# Teensy.net
KiCad netlist of a schematic drawn in Altium Designer
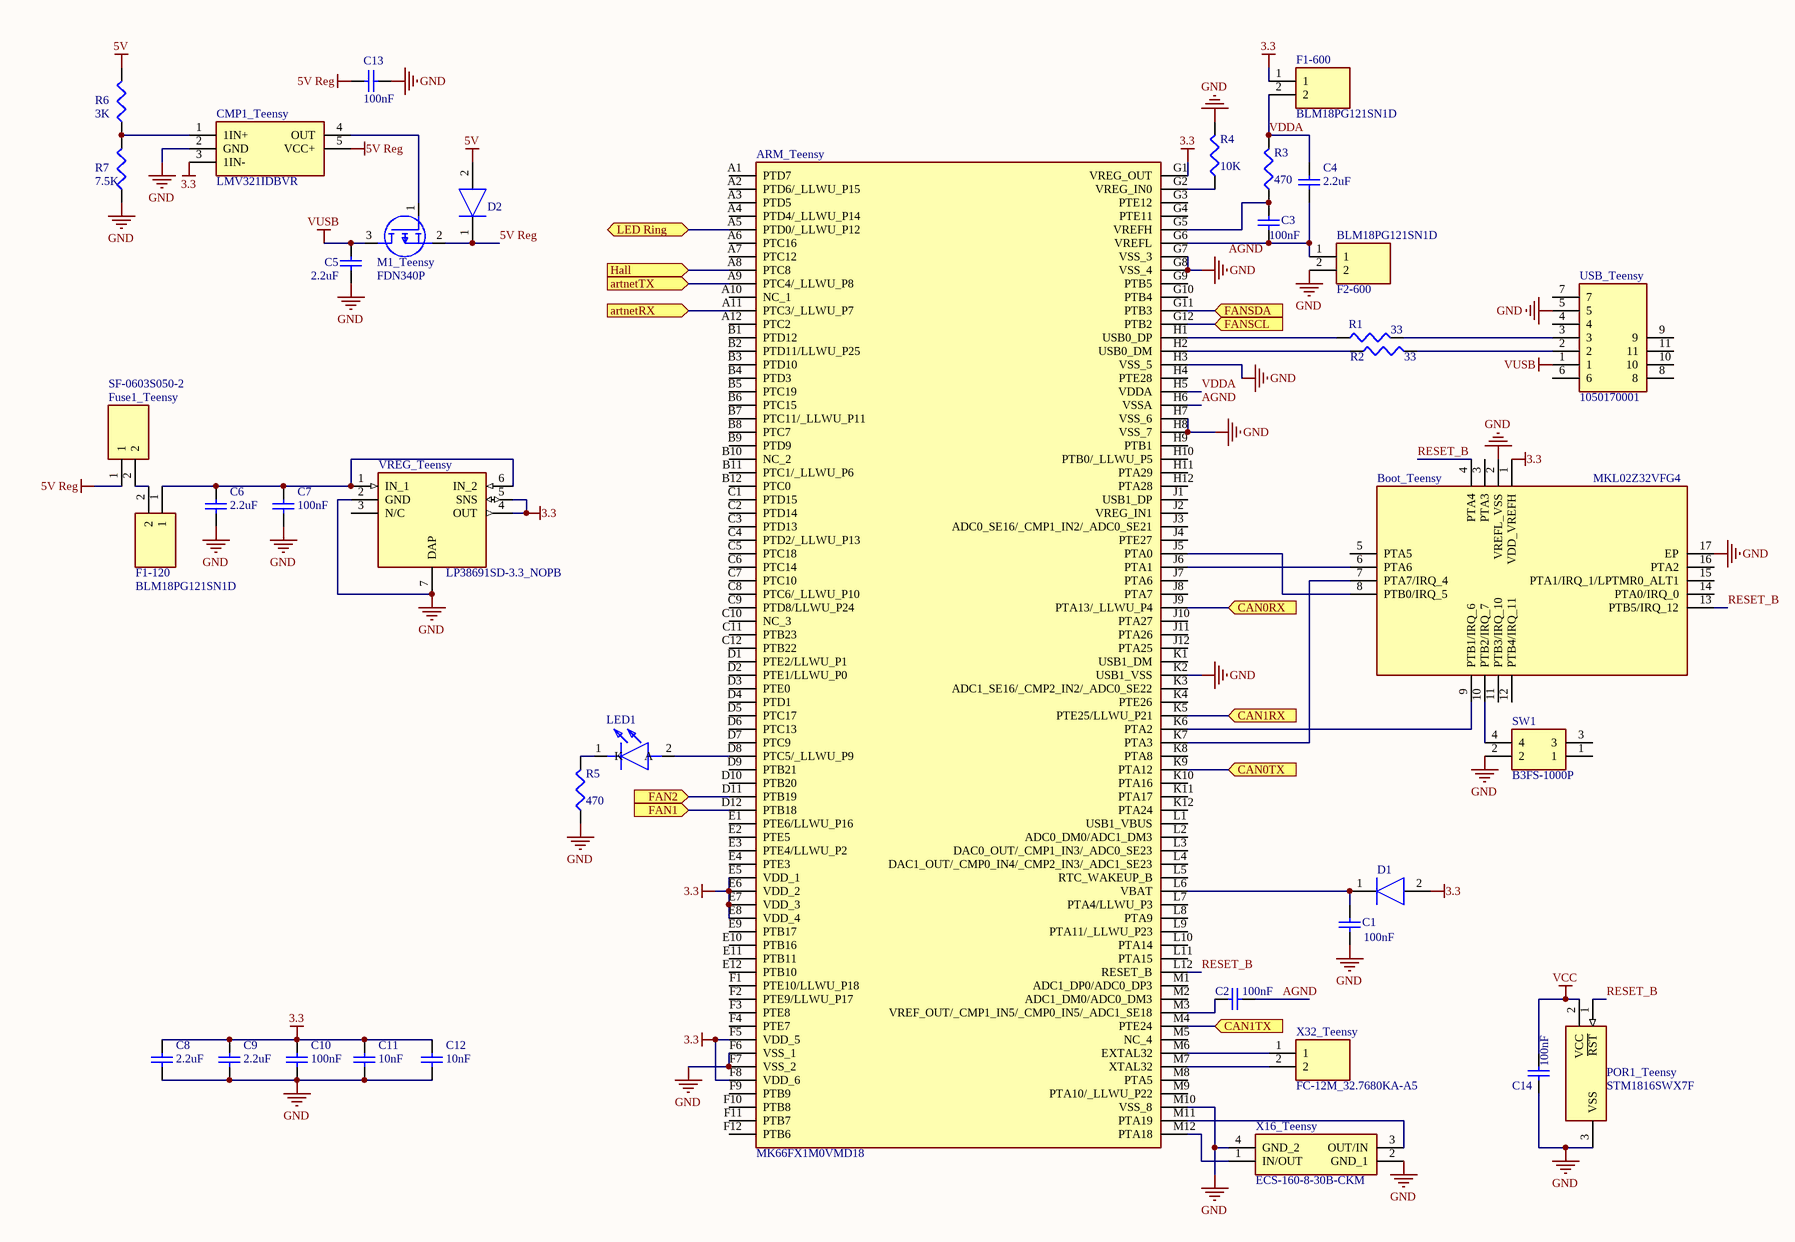
[diagram p0: Teensy.SchDoc]

(export (version "E")
  (design (tool "Eeschema 10.0.6"))
  (components
    (comp (ref "ARM_Teensy")
      (value "MK66FX1M0VMD18")
      (footprint "LX1-Teensy:BGA144C100P12X12_1300X1300X170")
      (description "Integrated Circuit")
      (fields (field (name "MOUSER PART NUMBER") "841-MK66FX1M0VMD18"))
      (libsource (lib "LX1-Teensy") (part "MK66FX1M0VMD18"))
    )
    (comp (ref "Boot_Teensy")
      (value "MKL02Z32VFG4")
      (footprint "LX1-Teensy:QFN50P300X300X65-17N-D")
      (description "Integrated Circuit")
      (fields
        (field (name "MOUSER PART NUMBER") "841-MKL02Z32VFG4")
        (field (name "RS PART NUMBER") "7884723P")
      )
      (libsource (lib "LX1-Teensy") (part "MKL02Z32VFG4"))
    )
    (comp (ref "C1")
      (value "100nF")
      (footprint "1608[0603]")
      (description "Capacitor (Semiconductor SIM Model)")
      (fields (field (name "Comment") "Cap Semi") (field (name "PUBLISHER") "Altium Limited"))
      (libsource (lib "Miscellaneous Devices") (part "Cap Semi"))
    )
    (comp (ref "C2")
      (value "100nF")
      (footprint "1608[0603]")
      (description "Capacitor (Semiconductor SIM Model)")
      (fields (field (name "Comment") "Cap Semi") (field (name "PUBLISHER") "Altium Limited"))
      (libsource (lib "Miscellaneous Devices") (part "Cap Semi"))
    )
    (comp (ref "C3")
      (value "100nF")
      (footprint "1608[0603]")
      (description "Capacitor (Semiconductor SIM Model)")
      (fields (field (name "Comment") "Cap Semi") (field (name "PUBLISHER") "Altium Limited"))
      (libsource (lib "Miscellaneous Devices") (part "Cap Semi"))
    )
    (comp (ref "C4")
      (value "2.2uF")
      (footprint "1608[0603]")
      (description "Capacitor (Semiconductor SIM Model)")
      (fields (field (name "Comment") "Cap Semi") (field (name "PUBLISHER") "Altium Limited"))
      (libsource (lib "Miscellaneous Devices") (part "Cap Semi"))
    )
    (comp (ref "C5")
      (value "2.2uF")
      (footprint "1608[0603]")
      (description "Capacitor (Semiconductor SIM Model)")
      (fields (field (name "Comment") "Cap Semi") (field (name "PUBLISHER") "Altium Limited"))
      (libsource (lib "Miscellaneous Devices") (part "Cap Semi"))
    )
    (comp (ref "C6")
      (value "2.2uF")
      (footprint "1608[0603]")
      (description "Capacitor (Semiconductor SIM Model)")
      (fields (field (name "Comment") "Cap Semi") (field (name "PUBLISHER") "Altium Limited"))
      (libsource (lib "Miscellaneous Devices") (part "Cap Semi"))
    )
    (comp (ref "C7")
      (value "100nF")
      (footprint "1608[0603]")
      (description "Capacitor (Semiconductor SIM Model)")
      (fields (field (name "Comment") "Cap Semi") (field (name "PUBLISHER") "Altium Limited"))
      (libsource (lib "Miscellaneous Devices") (part "Cap Semi"))
    )
    (comp (ref "C8")
      (value "2.2uF")
      (footprint "1608[0603]")
      (description "Capacitor (Semiconductor SIM Model)")
      (fields (field (name "Comment") "Cap Semi") (field (name "PUBLISHER") "Altium Limited"))
      (libsource (lib "Miscellaneous Devices") (part "Cap Semi"))
    )
    (comp (ref "C9")
      (value "2.2uF")
      (footprint "1608[0603]")
      (description "Capacitor (Semiconductor SIM Model)")
      (fields (field (name "Comment") "Cap Semi") (field (name "PUBLISHER") "Altium Limited"))
      (libsource (lib "Miscellaneous Devices") (part "Cap Semi"))
    )
    (comp (ref "C10")
      (value "100nF")
      (footprint "1608[0603]")
      (description "Capacitor (Semiconductor SIM Model)")
      (fields (field (name "Comment") "Cap Semi") (field (name "PUBLISHER") "Altium Limited"))
      (libsource (lib "Miscellaneous Devices") (part "Cap Semi"))
    )
    (comp (ref "C11")
      (value "10nF")
      (footprint "1608[0603]")
      (description "Capacitor (Semiconductor SIM Model)")
      (fields (field (name "Comment") "Cap Semi") (field (name "PUBLISHER") "Altium Limited"))
      (libsource (lib "Miscellaneous Devices") (part "Cap Semi"))
    )
    (comp (ref "C12")
      (value "10nF")
      (footprint "1608[0603]")
      (description "Capacitor (Semiconductor SIM Model)")
      (fields (field (name "Comment") "Cap Semi") (field (name "PUBLISHER") "Altium Limited"))
      (libsource (lib "Miscellaneous Devices") (part "Cap Semi"))
    )
    (comp (ref "C13")
      (value "100nF")
      (footprint "1608[0603]")
      (description "Capacitor (Semiconductor SIM Model)")
      (fields (field (name "Comment") "Cap Semi") (field (name "PUBLISHER") "Altium Limited"))
      (libsource (lib "Miscellaneous Devices") (part "Cap Semi"))
    )
    (comp (ref "C14")
      (value "100nF")
      (footprint "1608[0603]")
      (description "Capacitor (Semiconductor SIM Model)")
      (fields (field (name "Comment") "Cap Semi") (field (name "PUBLISHER") "Altium Limited"))
      (libsource (lib "Miscellaneous Devices") (part "Cap Semi"))
    )
    (comp (ref "CMP1_Teensy")
      (value "LMV321IDBVR")
      (footprint "LX1-PowerSelect:SOT95P280X145-5N")
      (description "Integrated Circuit")
      (fields (field (name "MOUSER PART NUMBER") "595-LMV321IDBVR"))
      (libsource (lib "LX1-PowerSelect") (part "LMV321IDBVR"))
    )
    (comp (ref "D1")
      (value "NRVTS260ESFT1G")
      (footprint "LX1-Teensy:SODFL3616X98N")
      (description "Diode")
      (fields
        (field (name "MOUSER PART NUMBER") "863-NRVTS260ESFT1G")
        (field (name "RS PART NUMBER") "8673243P")
      )
      (libsource (lib "LX1-Teensy") (part "NRVTS260ESFT1G"))
    )
    (comp (ref "D2")
      (value "NRVTS260ESFT1G")
      (footprint "LX1-Teensy:SODFL3616X98N")
      (description "Diode")
      (fields
        (field (name "MOUSER PART NUMBER") "863-NRVTS260ESFT1G")
        (field (name "RS PART NUMBER") "8673243P")
      )
      (libsource (lib "LX1-Teensy") (part "NRVTS260ESFT1G"))
    )
    (comp (ref "F1-120")
      (value "BLM18PG121SN1D")
      (footprint "LX1-Teensy:BEADC1608X95N")
      (description "Filter")
      (fields
        (field (name "MOUSER PART NUMBER") "81-BLM18PG121SN1D")
        (field (name "RS PART NUMBER") "7241380P")
      )
      (libsource (lib "LX1-Teensy") (part "BLM18PG121SN1D"))
    )
    (comp (ref "F1-600")
      (value "BLM18PG121SN1D")
      (footprint "LX1-Teensy:BEADC1608X95N")
      (description "Filter")
      (fields
        (field (name "MOUSER PART NUMBER") "81-BLM18PG121SN1D")
        (field (name "RS PART NUMBER") "7241380P")
      )
      (libsource (lib "") (part "BLM18PG121SN1D_1"))
    )
    (comp (ref "F2-600")
      (value "BLM18PG121SN1D")
      (footprint "LX1-Teensy:BEADC1608X95N")
      (description "Filter")
      (fields
        (field (name "MOUSER PART NUMBER") "81-BLM18PG121SN1D")
        (field (name "RS PART NUMBER") "7241380P")
      )
      (libsource (lib "") (part "BLM18PG121SN1D_1"))
    )
    (comp (ref "Fuse1_Teensy")
      (value "SF-0603S050-2")
      (footprint "LX1-Teensy:FUSC1608X55N")
      (description "Fuse")
      (fields
        (field (name "MOUSER PART NUMBER") "652-SF-0603S050-2")
        (field (name "RS PART NUMBER") "8978989P")
      )
      (libsource (lib "LX1-Teensy") (part "SF-0603S050-2"))
    )
    (comp (ref "LED1")
      (value "HSMC-C190")
      (footprint "LX1-Teensy:LEDC1608X90N")
      (description "LED")
      (fields (field (name "MOUSER PART NUMBER") "630-HSMC-C190") (field (name "RS PART NUMBER") "6910391P"))
      (libsource (lib "LX1-Teensy") (part "HSMC-C190"))
    )
    (comp (ref "M1_Teensy")
      (value "FDN340P")
      (footprint "LX1-PowerSelect:SOT95P237X112-3N")
      (description "MOSFET (P-Channel)")
      (fields (field (name "MOUSER PART NUMBER") "512-FDN340P") (field (name "RS PART NUMBER") "6710435P"))
      (libsource (lib "LX1-PowerSelect") (part "FDN340P"))
    )
    (comp (ref "POR1_Teensy")
      (value "STM1816SWX7F")
      (footprint "LX1-PowerSelect:SOT103P237X112-3N")
      (description "Integrated Circuit")
      (fields
        (field (name "MOUSER PART NUMBER") "511-STM1816SWX7F")
        (field (name "RS PART NUMBER") "6248264")
      )
      (libsource (lib "LX1-PowerSelect") (part "STM1816SWX7F"))
    )
    (comp (ref "R1")
      (value "33")
      (footprint "J1-0603")
      (description "Resistor")
      (fields (field (name "Comment") "Res3") (field (name "PUBLISHER") "Altium Limited"))
      (libsource (lib "Miscellaneous Devices") (part "Res3"))
    )
    (comp (ref "R2")
      (value "33")
      (footprint "J1-0603")
      (description "Resistor")
      (fields (field (name "Comment") "Res3") (field (name "PUBLISHER") "Altium Limited"))
      (libsource (lib "Miscellaneous Devices") (part "Res3"))
    )
    (comp (ref "R3")
      (value "470")
      (footprint "J1-0603")
      (description "Resistor")
      (fields (field (name "Comment") "Res3") (field (name "PUBLISHER") "Altium Limited"))
      (libsource (lib "Miscellaneous Devices") (part "Res3"))
    )
    (comp (ref "R4")
      (value "10K")
      (footprint "J1-0603")
      (description "Resistor")
      (fields (field (name "Comment") "Res3") (field (name "PUBLISHER") "Altium Limited"))
      (libsource (lib "Miscellaneous Devices") (part "Res3"))
    )
    (comp (ref "R5")
      (value "470")
      (footprint "J1-0603")
      (description "Resistor")
      (fields (field (name "Comment") "Res3") (field (name "PUBLISHER") "Altium Limited"))
      (libsource (lib "Miscellaneous Devices") (part "Res3"))
    )
    (comp (ref "R6")
      (value "3K")
      (footprint "J1-0603")
      (description "Resistor")
      (fields (field (name "Comment") "Res3") (field (name "PUBLISHER") "Altium Limited"))
      (libsource (lib "Miscellaneous Devices") (part "Res3"))
    )
    (comp (ref "R7")
      (value "7.5K")
      (footprint "J1-0603")
      (description "Resistor")
      (fields (field (name "Comment") "Res3") (field (name "PUBLISHER") "Altium Limited"))
      (libsource (lib "Miscellaneous Devices") (part "Res3"))
    )
    (comp (ref "SW1")
      (value "B3FS-1000P")
      (footprint "LX1-Teensy:B3FS-1000P")
      (description "Switch")
      (fields (field (name "MOUSER PART NUMBER") "653-B3FS-1000P") (field (name "RS PART NUMBER") "6821254P"))
      (libsource (lib "LX1-Teensy") (part "B3FS-1000P"))
    )
    (comp (ref "USB_Teensy")
      (value "1050170001")
      (footprint "LX1-Teensy:MICROUSB-BTYPE")
      (description "Connector")
      (libsource (lib "LX1-Teensy") (part "1050170001"))
    )
    (comp (ref "VREG_Teensy")
      (value "LP38691SD-3.3_NOPB")
      (footprint "LX1-Teensy:SON95P300X300X80-7N")
      (description "Power Supply")
      (fields
        (field (name "MANUFACTURER_PART_NUMBER") "LP38691SD-3.3/NOPB")
        (field (name "MOUSER PART NUMBER") "926-38691SD-3.3/NOPB")
      )
      (libsource (lib "LX1-Teensy") (part "LP38691SD-3.3_NOPB"))
    )
    (comp (ref "X16_Teensy")
      (value "ECS-160-8-30B-CKM")
      (footprint "LX1-Teensy:ECS801830BAGNTR")
      (description "Crystal or Oscillator")
      (fields (field (name "MOUSER PART NUMBER") "520-160-8-30B-CKM"))
      (libsource (lib "LX1-Teensy") (part "ECS-160-8-30B-CKM"))
    )
    (comp (ref "X32_Teensy")
      (value "FC-12M_32.7680KA-A5")
      (footprint "LX1-Teensy:FC12M327680KAA5")
      (description "Crystal or Oscillator")
      (fields
        (field (name "MANUFACTURER_PART_NUMBER") "FC-12M 32.7680KA-A5")
        (field (name "MOUSER PART NUMBER") "732-FC-12M32.768KAA5")
      )
      (libsource (lib "LX1-Teensy") (part "FC-12M_32.7680KA-A5"))
    )
  )
  (nets
    (net (code "1") (name "/AGND") (class "Default")
      (node (ref "ARM_Teensy") (pin "H6") (pinfunction "VSSA_H6") (pintype "passive"))
      (node (ref "C2") (pin "2") (pinfunction "2_2") (pintype "passive"))
    )
    (net (code "2") (name "/CAN0RX") (class "Default")
      (node (ref "ARM_Teensy") (pin "J9") (pinfunction "PTA13/_LLWU_P4_J9") (pintype "passive"))
    )
    (net (code "3") (name "/CAN0TX") (class "Default")
      (node (ref "ARM_Teensy") (pin "K9") (pinfunction "PTA12_K9") (pintype "passive"))
    )
    (net (code "4") (name "/CAN1RX") (class "Default")
      (node (ref "ARM_Teensy") (pin "K5") (pinfunction "PTE25/LLWU_P21_K5") (pintype "passive"))
    )
    (net (code "5") (name "/CAN1TX") (class "Default")
      (node (ref "ARM_Teensy") (pin "M4") (pinfunction "PTE24_M4") (pintype "passive"))
    )
    (net (code "6") (name "/FAN1") (class "Default")
      (node (ref "ARM_Teensy") (pin "D12") (pinfunction "PTB18_D12") (pintype "passive"))
    )
    (net (code "7") (name "/FAN2") (class "Default")
      (node (ref "ARM_Teensy") (pin "D11") (pinfunction "PTB19_D11") (pintype "passive"))
    )
    (net (code "8") (name "/FANSCL") (class "Default")
      (node (ref "ARM_Teensy") (pin "G12") (pinfunction "PTB2_G12") (pintype "passive"))
    )
    (net (code "9") (name "/FANSDA") (class "Default")
      (node (ref "ARM_Teensy") (pin "G11") (pinfunction "PTB3_G11") (pintype "passive"))
    )
    (net (code "10") (name "/Hall") (class "Default")
      (node (ref "ARM_Teensy") (pin "A8") (pinfunction "PTC8_A8") (pintype "passive"))
    )
    (net (code "11") (name "/LED Ring") (class "Default")
      (node (ref "ARM_Teensy") (pin "A5") (pinfunction "PTD0/_LLWU_P12_A5") (pintype "passive"))
    )
    (net (code "12") (name "/RESET_B") (class "Default")
      (node (ref "ARM_Teensy") (pin "L12") (pinfunction "RESET_B_L12") (pintype "passive"))
      (node (ref "Boot_Teensy") (pin "13") (pinfunction "PTB5/IRQ_12_13") (pintype "passive"))
      (node (ref "Boot_Teensy") (pin "4") (pinfunction "PTA4_4") (pintype "passive"))
      (node (ref "POR1_Teensy") (pin "1") (pinfunction "~{RST}_1") (pintype "input"))
    )
    (net (code "13") (name "/VDDA") (class "Default")
      (node (ref "ARM_Teensy") (pin "H5") (pinfunction "VDDA_H5") (pintype "passive"))
      (node (ref "C4") (pin "2") (pinfunction "2_2") (pintype "passive"))
      (node (ref "F1-600") (pin "2") (pinfunction "2_2") (pintype "passive"))
      (node (ref "R3") (pin "2") (pinfunction "2_2") (pintype "passive"))
    )
    (net (code "14") (name "/artnetRX") (class "Default")
      (node (ref "ARM_Teensy") (pin "A11") (pinfunction "PTC3/_LLWU_P7_A11") (pintype "passive"))
    )
    (net (code "15") (name "/artnetTX") (class "Default")
      (node (ref "ARM_Teensy") (pin "A9") (pinfunction "PTC4/_LLWU_P8_A9") (pintype "passive"))
    )
    (net (code "16") (name "3.3") (class "Default")
      (node (ref "ARM_Teensy") (pin "E5") (pinfunction "VDD_1_E5") (pintype "passive"))
      (node (ref "ARM_Teensy") (pin "E6") (pinfunction "VDD_2_E6") (pintype "passive"))
      (node (ref "ARM_Teensy") (pin "E7") (pinfunction "VDD_3_E7") (pintype "passive"))
      (node (ref "ARM_Teensy") (pin "E8") (pinfunction "VDD_4_E8") (pintype "passive"))
      (node (ref "ARM_Teensy") (pin "F5") (pinfunction "VDD_5_F5") (pintype "passive"))
      (node (ref "ARM_Teensy") (pin "F8") (pinfunction "VDD_6_F8") (pintype "passive"))
      (node (ref "ARM_Teensy") (pin "G1") (pinfunction "VREG_OUT_G1") (pintype "passive"))
      (node (ref "Boot_Teensy") (pin "1") (pinfunction "VDD_VREFH_1") (pintype "passive"))
      (node (ref "C10") (pin "2") (pinfunction "2_2") (pintype "passive"))
      (node (ref "C11") (pin "2") (pinfunction "2_2") (pintype "passive"))
      (node (ref "C12") (pin "2") (pinfunction "2_2") (pintype "passive"))
      (node (ref "C8") (pin "2") (pinfunction "2_2") (pintype "passive"))
      (node (ref "C9") (pin "2") (pinfunction "2_2") (pintype "passive"))
      (node (ref "CMP1_Teensy") (pin "3") (pinfunction "1IN-_3") (pintype "passive"))
      (node (ref "D1") (pin "2") (pinfunction "A_2") (pintype "passive"))
      (node (ref "F1-600") (pin "1") (pinfunction "1_1") (pintype "passive"))
      (node (ref "VREG_Teensy") (pin "4") (pinfunction "OUT_4") (pintype "output"))
      (node (ref "VREG_Teensy") (pin "5") (pinfunction "SNS_5") (pintype "bidirectional"))
    )
    (net (code "17") (name "5V") (class "Default")
      (node (ref "D2") (pin "2") (pinfunction "A_2") (pintype "passive"))
      (node (ref "R6") (pin "2") (pinfunction "2_2") (pintype "passive"))
    )
    (net (code "18") (name "5V Reg") (class "Default")
      (node (ref "C13") (pin "2") (pinfunction "2_2") (pintype "passive"))
      (node (ref "CMP1_Teensy") (pin "5") (pinfunction "VCC+_5") (pintype "passive"))
      (node (ref "D2") (pin "1") (pinfunction "K_1") (pintype "passive"))
      (node (ref "Fuse1_Teensy") (pin "1") (pinfunction "1_1") (pintype "passive"))
      (node (ref "M1_Teensy") (pin "2") (pinfunction "S_2") (pintype "passive"))
    )
    (net (code "19") (name "GND") (class "Default")
      (node (ref "ARM_Teensy") (pin "F6") (pinfunction "VSS_1_F6") (pintype "passive"))
      (node (ref "ARM_Teensy") (pin "F7") (pinfunction "VSS_2_F7") (pintype "passive"))
      (node (ref "ARM_Teensy") (pin "G7") (pinfunction "VSS_3_G7") (pintype "passive"))
      (node (ref "ARM_Teensy") (pin "G8") (pinfunction "VSS_4_G8") (pintype "passive"))
      (node (ref "ARM_Teensy") (pin "H3") (pinfunction "VSS_5_H3") (pintype "passive"))
      (node (ref "ARM_Teensy") (pin "H7") (pinfunction "VSS_6_H7") (pintype "passive"))
      (node (ref "ARM_Teensy") (pin "H8") (pinfunction "VSS_7_H8") (pintype "passive"))
      (node (ref "ARM_Teensy") (pin "K2") (pinfunction "USB1_VSS_K2") (pintype "passive"))
      (node (ref "ARM_Teensy") (pin "M10") (pinfunction "VSS_8_M10") (pintype "passive"))
      (node (ref "Boot_Teensy") (pin "17") (pinfunction "EP_17") (pintype "passive"))
      (node (ref "Boot_Teensy") (pin "2") (pinfunction "VREFL_VSS_2") (pintype "passive"))
      (node (ref "C1") (pin "1") (pinfunction "1_1") (pintype "passive"))
      (node (ref "C10") (pin "1") (pinfunction "1_1") (pintype "passive"))
      (node (ref "C11") (pin "1") (pinfunction "1_1") (pintype "passive"))
      (node (ref "C12") (pin "1") (pinfunction "1_1") (pintype "passive"))
      (node (ref "C13") (pin "1") (pinfunction "1_1") (pintype "passive"))
      (node (ref "C14") (pin "1") (pinfunction "1_1") (pintype "passive"))
      (node (ref "C5") (pin "2") (pinfunction "2_2") (pintype "passive"))
      (node (ref "C6") (pin "1") (pinfunction "1_1") (pintype "passive"))
      (node (ref "C7") (pin "1") (pinfunction "1_1") (pintype "passive"))
      (node (ref "C8") (pin "1") (pinfunction "1_1") (pintype "passive"))
      (node (ref "C9") (pin "1") (pinfunction "1_1") (pintype "passive"))
      (node (ref "CMP1_Teensy") (pin "2") (pinfunction "GND_2") (pintype "passive"))
      (node (ref "F2-600") (pin "2") (pinfunction "2_2") (pintype "passive"))
      (node (ref "POR1_Teensy") (pin "3") (pinfunction "VSS_3") (pintype "power_in"))
      (node (ref "R4") (pin "2") (pinfunction "2_2") (pintype "passive"))
      (node (ref "R5") (pin "1") (pinfunction "1_1") (pintype "passive"))
      (node (ref "R7") (pin "1") (pinfunction "1_1") (pintype "passive"))
      (node (ref "SW1") (pin "2") (pinfunction "2_2") (pintype "passive"))
      (node (ref "USB_Teensy") (pin "5") (pinfunction "5_5") (pintype "passive"))
      (node (ref "VREG_Teensy") (pin "2") (pinfunction "GND_2") (pintype "power_in"))
      (node (ref "VREG_Teensy") (pin "7") (pinfunction "DAP_7") (pintype "passive"))
      (node (ref "X16_Teensy") (pin "2") (pinfunction "GND_1_2") (pintype "passive"))
      (node (ref "X16_Teensy") (pin "4") (pinfunction "GND_2_4") (pintype "passive"))
    )
    (net (code "20") (name "Net-(ARM_Teensy-EXTAL32)") (class "Default")
      (node (ref "ARM_Teensy") (pin "M6") (pinfunction "EXTAL32_M6") (pintype "passive"))
      (node (ref "X32_Teensy") (pin "1") (pinfunction "1_1") (pintype "passive"))
    )
    (net (code "21") (name "Net-(ARM_Teensy-PTA0)") (class "Default")
      (node (ref "ARM_Teensy") (pin "J5") (pinfunction "PTA0_J5") (pintype "passive"))
      (node (ref "Boot_Teensy") (pin "8") (pinfunction "PTB0/IRQ_5_8") (pintype "passive"))
    )
    (net (code "22") (name "Net-(ARM_Teensy-PTA1)") (class "Default")
      (node (ref "ARM_Teensy") (pin "J6") (pinfunction "PTA1_J6") (pintype "passive"))
      (node (ref "Boot_Teensy") (pin "6") (pinfunction "PTA6_6") (pintype "passive"))
    )
    (net (code "23") (name "Net-(ARM_Teensy-PTA2)") (class "Default")
      (node (ref "ARM_Teensy") (pin "K6") (pinfunction "PTA2_K6") (pintype "passive"))
      (node (ref "Boot_Teensy") (pin "9") (pinfunction "PTB1/IRQ_6_9") (pintype "passive"))
    )
    (net (code "24") (name "Net-(ARM_Teensy-PTA3)") (class "Default")
      (node (ref "ARM_Teensy") (pin "K7") (pinfunction "PTA3_K7") (pintype "passive"))
      (node (ref "Boot_Teensy") (pin "7") (pinfunction "PTA7/IRQ_4_7") (pintype "passive"))
    )
    (net (code "25") (name "Net-(ARM_Teensy-PTA18)") (class "Default")
      (node (ref "ARM_Teensy") (pin "M12") (pinfunction "PTA18_M12") (pintype "passive"))
      (node (ref "X16_Teensy") (pin "1") (pinfunction "IN/OUT_1") (pintype "passive"))
    )
    (net (code "26") (name "Net-(ARM_Teensy-PTA19)") (class "Default")
      (node (ref "ARM_Teensy") (pin "M11") (pinfunction "PTA19_M11") (pintype "passive"))
      (node (ref "X16_Teensy") (pin "3") (pinfunction "OUT/IN_3") (pintype "passive"))
    )
    (net (code "27") (name "Net-(ARM_Teensy-PTC5{slash}_LLWU_P9)") (class "Default")
      (node (ref "ARM_Teensy") (pin "D8") (pinfunction "PTC5/_LLWU_P9_D8") (pintype "passive"))
      (node (ref "LED1") (pin "2") (pinfunction "A_2") (pintype "passive"))
    )
    (net (code "28") (name "Net-(ARM_Teensy-USB0_DM)") (class "Default")
      (node (ref "ARM_Teensy") (pin "H2") (pinfunction "USB0_DM_H2") (pintype "passive"))
      (node (ref "R2") (pin "1") (pinfunction "1_1") (pintype "passive"))
    )
    (net (code "29") (name "Net-(ARM_Teensy-USB0_DP)") (class "Default")
      (node (ref "ARM_Teensy") (pin "H1") (pinfunction "USB0_DP_H1") (pintype "passive"))
      (node (ref "R1") (pin "1") (pinfunction "1_1") (pintype "passive"))
    )
    (net (code "30") (name "Net-(ARM_Teensy-VBAT)") (class "Default")
      (node (ref "ARM_Teensy") (pin "L6") (pinfunction "VBAT_L6") (pintype "passive"))
      (node (ref "C1") (pin "2") (pinfunction "2_2") (pintype "passive"))
      (node (ref "D1") (pin "1") (pinfunction "K_1") (pintype "passive"))
    )
    (net (code "31") (name "Net-(ARM_Teensy-VREFH)") (class "Default")
      (node (ref "ARM_Teensy") (pin "G5") (pinfunction "VREFH_G5") (pintype "passive"))
      (node (ref "C3") (pin "2") (pinfunction "2_2") (pintype "passive"))
      (node (ref "R3") (pin "1") (pinfunction "1_1") (pintype "passive"))
    )
    (net (code "32") (name "Net-(ARM_Teensy-VREFL)") (class "Default")
      (node (ref "ARM_Teensy") (pin "G6") (pinfunction "VREFL_G6") (pintype "passive"))
      (node (ref "C3") (pin "1") (pinfunction "1_1") (pintype "passive"))
      (node (ref "C4") (pin "1") (pinfunction "1_1") (pintype "passive"))
      (node (ref "F2-600") (pin "1") (pinfunction "1_1") (pintype "passive"))
    )
    (net (code "33") (name "Net-(ARM_Teensy-VREF_OUT{slash}_CMP1_IN5{slash}_CMP0_IN5{slash}_ADC1_SE18)") (class "Default")
      (node (ref "ARM_Teensy") (pin "M3") (pinfunction "VREF_OUT/_CMP1_IN5/_CMP0_IN5/_ADC1_SE18_M3") (pintype "passive"))
      (node (ref "C2") (pin "1") (pinfunction "1_1") (pintype "passive"))
    )
    (net (code "34") (name "Net-(ARM_Teensy-VREG_IN0)") (class "Default")
      (node (ref "ARM_Teensy") (pin "G2") (pinfunction "VREG_IN0_G2") (pintype "passive"))
      (node (ref "R4") (pin "1") (pinfunction "1_1") (pintype "passive"))
    )
    (net (code "35") (name "Net-(ARM_Teensy-XTAL32)") (class "Default")
      (node (ref "ARM_Teensy") (pin "M7") (pinfunction "XTAL32_M7") (pintype "passive"))
      (node (ref "X32_Teensy") (pin "2") (pinfunction "2_2") (pintype "passive"))
    )
    (net (code "36") (name "Net-(Boot_Teensy-PTB2{slash}IRQ_7)") (class "Default")
      (node (ref "Boot_Teensy") (pin "10") (pinfunction "PTB2/IRQ_7_10") (pintype "passive"))
      (node (ref "SW1") (pin "4") (pinfunction "4_4") (pintype "passive"))
    )
    (net (code "37") (name "Net-(CMP1_Teensy-1IN+)") (class "Default")
      (node (ref "CMP1_Teensy") (pin "1") (pinfunction "1IN+_1") (pintype "passive"))
      (node (ref "R6") (pin "1") (pinfunction "1_1") (pintype "passive"))
      (node (ref "R7") (pin "2") (pinfunction "2_2") (pintype "passive"))
    )
    (net (code "38") (name "Net-(CMP1_Teensy-OUT)") (class "Default")
      (node (ref "CMP1_Teensy") (pin "4") (pinfunction "OUT_4") (pintype "passive"))
      (node (ref "M1_Teensy") (pin "1") (pinfunction "G_1") (pintype "passive"))
    )
    (net (code "39") (name "Net-(F1-120-Pad2)") (class "Default")
      (node (ref "F1-120") (pin "2") (pinfunction "2_2") (pintype "passive"))
      (node (ref "Fuse1_Teensy") (pin "2") (pinfunction "2_2") (pintype "passive"))
    )
    (net (code "40") (name "Net-(LED1-K)") (class "Default")
      (node (ref "LED1") (pin "1") (pinfunction "K_1") (pintype "passive"))
      (node (ref "R5") (pin "2") (pinfunction "2_2") (pintype "passive"))
    )
    (net (code "41") (name "Net-(R1-Pad2)") (class "Default")
      (node (ref "R1") (pin "2") (pinfunction "2_2") (pintype "passive"))
      (node (ref "USB_Teensy") (pin "3") (pinfunction "3_3") (pintype "passive"))
    )
    (net (code "42") (name "Net-(R2-Pad2)") (class "Default")
      (node (ref "R2") (pin "2") (pinfunction "2_2") (pintype "passive"))
      (node (ref "USB_Teensy") (pin "2") (pinfunction "2_2") (pintype "passive"))
    )
    (net (code "43") (name "Net-(VREG_Teensy-IN_1)") (class "Default")
      (node (ref "C6") (pin "2") (pinfunction "2_2") (pintype "passive"))
      (node (ref "C7") (pin "2") (pinfunction "2_2") (pintype "passive"))
      (node (ref "F1-120") (pin "1") (pinfunction "1_1") (pintype "passive"))
      (node (ref "VREG_Teensy") (pin "1") (pinfunction "IN_1_1") (pintype "input"))
      (node (ref "VREG_Teensy") (pin "6") (pinfunction "IN_2_6") (pintype "input"))
    )
    (net (code "44") (name "VCC") (class "Default")
      (node (ref "C14") (pin "2") (pinfunction "2_2") (pintype "passive"))
      (node (ref "POR1_Teensy") (pin "2") (pinfunction "VCC_2") (pintype "power_in"))
    )
    (net (code "45") (name "VUSB") (class "Default")
      (node (ref "C5") (pin "1") (pinfunction "1_1") (pintype "passive"))
      (node (ref "M1_Teensy") (pin "3") (pinfunction "D_3") (pintype "passive"))
      (node (ref "USB_Teensy") (pin "1") (pinfunction "1_1") (pintype "passive"))
    )
    (net (code "46") (name "unconnected-(ARM_Teensy-ADC0_DM0{slash}ADC1_DM3-PadL2)") (class "Default")
      (node (ref "ARM_Teensy") (pin "L2") (pinfunction "ADC0_DM0/ADC1_DM3_L2") (pintype "passive"))
    )
    (net (code "47") (name "unconnected-(ARM_Teensy-ADC0_SE16{slash}_CMP1_IN2{slash}_ADC0_SE21-PadJ3)") (class "Default")
      (node (ref "ARM_Teensy") (pin "J3") (pinfunction "ADC0_SE16/_CMP1_IN2/_ADC0_SE21_J3") (pintype "passive"))
    )
    (net (code "48") (name "unconnected-(ARM_Teensy-ADC1_DM0{slash}ADC0_DM3-PadM2)") (class "Default")
      (node (ref "ARM_Teensy") (pin "M2") (pinfunction "ADC1_DM0/ADC0_DM3_M2") (pintype "passive"))
    )
    (net (code "49") (name "unconnected-(ARM_Teensy-ADC1_DP0{slash}ADC0_DP3-PadM1)") (class "Default")
      (node (ref "ARM_Teensy") (pin "M1") (pinfunction "ADC1_DP0/ADC0_DP3_M1") (pintype "passive"))
    )
    (net (code "50") (name "unconnected-(ARM_Teensy-ADC1_SE16{slash}_CMP2_IN2{slash}_ADC0_SE22-PadK3)") (class "Default")
      (node (ref "ARM_Teensy") (pin "K3") (pinfunction "ADC1_SE16/_CMP2_IN2/_ADC0_SE22_K3") (pintype "passive"))
    )
    (net (code "51") (name "unconnected-(ARM_Teensy-DAC0_OUT{slash}_CMP1_IN3{slash}_ADC0_SE23-PadL3)") (class "Default")
      (node (ref "ARM_Teensy") (pin "L3") (pinfunction "DAC0_OUT/_CMP1_IN3/_ADC0_SE23_L3") (pintype "passive"))
    )
    (net (code "52") (name "unconnected-(ARM_Teensy-DAC1_OUT{slash}_CMP0_IN4{slash}_CMP2_IN3{slash}_ADC1_SE23-PadL4)") (class "Default")
      (node (ref "ARM_Teensy") (pin "L4") (pinfunction "DAC1_OUT/_CMP0_IN4/_CMP2_IN3/_ADC1_SE23_L4") (pintype "passive"))
    )
    (net (code "53") (name "unconnected-(ARM_Teensy-NC_1-PadA10)") (class "Default")
      (node (ref "ARM_Teensy") (pin "A10") (pinfunction "NC_1_A10") (pintype "passive"))
    )
    (net (code "54") (name "unconnected-(ARM_Teensy-NC_2-PadB10)") (class "Default")
      (node (ref "ARM_Teensy") (pin "B10") (pinfunction "NC_2_B10") (pintype "passive"))
    )
    (net (code "55") (name "unconnected-(ARM_Teensy-NC_3-PadC10)") (class "Default")
      (node (ref "ARM_Teensy") (pin "C10") (pinfunction "NC_3_C10") (pintype "passive"))
    )
    (net (code "56") (name "unconnected-(ARM_Teensy-NC_4-PadM5)") (class "Default")
      (node (ref "ARM_Teensy") (pin "M5") (pinfunction "NC_4_M5") (pintype "passive"))
    )
    (net (code "57") (name "unconnected-(ARM_Teensy-PTA4{slash}LLWU_P3-PadL7)") (class "Default")
      (node (ref "ARM_Teensy") (pin "L7") (pinfunction "PTA4/LLWU_P3_L7") (pintype "passive"))
    )
    (net (code "58") (name "unconnected-(ARM_Teensy-PTA5-PadM8)") (class "Default")
      (node (ref "ARM_Teensy") (pin "M8") (pinfunction "PTA5_M8") (pintype "passive"))
    )
    (net (code "59") (name "unconnected-(ARM_Teensy-PTA6-PadJ7)") (class "Default")
      (node (ref "ARM_Teensy") (pin "J7") (pinfunction "PTA6_J7") (pintype "passive"))
    )
    (net (code "60") (name "unconnected-(ARM_Teensy-PTA7-PadJ8)") (class "Default")
      (node (ref "ARM_Teensy") (pin "J8") (pinfunction "PTA7_J8") (pintype "passive"))
    )
    (net (code "61") (name "unconnected-(ARM_Teensy-PTA8-PadK8)") (class "Default")
      (node (ref "ARM_Teensy") (pin "K8") (pinfunction "PTA8_K8") (pintype "passive"))
    )
    (net (code "62") (name "unconnected-(ARM_Teensy-PTA9-PadL8)") (class "Default")
      (node (ref "ARM_Teensy") (pin "L8") (pinfunction "PTA9_L8") (pintype "passive"))
    )
    (net (code "63") (name "unconnected-(ARM_Teensy-PTA10{slash}_LLWU_P22-PadM9)") (class "Default")
      (node (ref "ARM_Teensy") (pin "M9") (pinfunction "PTA10/_LLWU_P22_M9") (pintype "passive"))
    )
    (net (code "64") (name "unconnected-(ARM_Teensy-PTA11{slash}_LLWU_P23-PadL9)") (class "Default")
      (node (ref "ARM_Teensy") (pin "L9") (pinfunction "PTA11/_LLWU_P23_L9") (pintype "passive"))
    )
    (net (code "65") (name "unconnected-(ARM_Teensy-PTA14-PadL10)") (class "Default")
      (node (ref "ARM_Teensy") (pin "L10") (pinfunction "PTA14_L10") (pintype "passive"))
    )
    (net (code "66") (name "unconnected-(ARM_Teensy-PTA15-PadL11)") (class "Default")
      (node (ref "ARM_Teensy") (pin "L11") (pinfunction "PTA15_L11") (pintype "passive"))
    )
    (net (code "67") (name "unconnected-(ARM_Teensy-PTA16-PadK10)") (class "Default")
      (node (ref "ARM_Teensy") (pin "K10") (pinfunction "PTA16_K10") (pintype "passive"))
    )
    (net (code "68") (name "unconnected-(ARM_Teensy-PTA17-PadK11)") (class "Default")
      (node (ref "ARM_Teensy") (pin "K11") (pinfunction "PTA17_K11") (pintype "passive"))
    )
    (net (code "69") (name "unconnected-(ARM_Teensy-PTA24-PadK12)") (class "Default")
      (node (ref "ARM_Teensy") (pin "K12") (pinfunction "PTA24_K12") (pintype "passive"))
    )
    (net (code "70") (name "unconnected-(ARM_Teensy-PTA25-PadJ12)") (class "Default")
      (node (ref "ARM_Teensy") (pin "J12") (pinfunction "PTA25_J12") (pintype "passive"))
    )
    (net (code "71") (name "unconnected-(ARM_Teensy-PTA26-PadJ11)") (class "Default")
      (node (ref "ARM_Teensy") (pin "J11") (pinfunction "PTA26_J11") (pintype "passive"))
    )
    (net (code "72") (name "unconnected-(ARM_Teensy-PTA27-PadJ10)") (class "Default")
      (node (ref "ARM_Teensy") (pin "J10") (pinfunction "PTA27_J10") (pintype "passive"))
    )
    (net (code "73") (name "unconnected-(ARM_Teensy-PTA28-PadH12)") (class "Default")
      (node (ref "ARM_Teensy") (pin "H12") (pinfunction "PTA28_H12") (pintype "passive"))
    )
    (net (code "74") (name "unconnected-(ARM_Teensy-PTA29-PadH11)") (class "Default")
      (node (ref "ARM_Teensy") (pin "H11") (pinfunction "PTA29_H11") (pintype "passive"))
    )
    (net (code "75") (name "unconnected-(ARM_Teensy-PTB0{slash}_LLWU_P5-PadH10)") (class "Default")
      (node (ref "ARM_Teensy") (pin "H10") (pinfunction "PTB0/_LLWU_P5_H10") (pintype "passive"))
    )
    (net (code "76") (name "unconnected-(ARM_Teensy-PTB1-PadH9)") (class "Default")
      (node (ref "ARM_Teensy") (pin "H9") (pinfunction "PTB1_H9") (pintype "passive"))
    )
    (net (code "77") (name "unconnected-(ARM_Teensy-PTB4-PadG10)") (class "Default")
      (node (ref "ARM_Teensy") (pin "G10") (pinfunction "PTB4_G10") (pintype "passive"))
    )
    (net (code "78") (name "unconnected-(ARM_Teensy-PTB5-PadG9)") (class "Default")
      (node (ref "ARM_Teensy") (pin "G9") (pinfunction "PTB5_G9") (pintype "passive"))
    )
    (net (code "79") (name "unconnected-(ARM_Teensy-PTB6-PadF12)") (class "Default")
      (node (ref "ARM_Teensy") (pin "F12") (pinfunction "PTB6_F12") (pintype "passive"))
    )
    (net (code "80") (name "unconnected-(ARM_Teensy-PTB7-PadF11)") (class "Default")
      (node (ref "ARM_Teensy") (pin "F11") (pinfunction "PTB7_F11") (pintype "passive"))
    )
    (net (code "81") (name "unconnected-(ARM_Teensy-PTB8-PadF10)") (class "Default")
      (node (ref "ARM_Teensy") (pin "F10") (pinfunction "PTB8_F10") (pintype "passive"))
    )
    (net (code "82") (name "unconnected-(ARM_Teensy-PTB9-PadF9)") (class "Default")
      (node (ref "ARM_Teensy") (pin "F9") (pinfunction "PTB9_F9") (pintype "passive"))
    )
    (net (code "83") (name "unconnected-(ARM_Teensy-PTB10-PadE12)") (class "Default")
      (node (ref "ARM_Teensy") (pin "E12") (pinfunction "PTB10_E12") (pintype "passive"))
    )
    (net (code "84") (name "unconnected-(ARM_Teensy-PTB11-PadE11)") (class "Default")
      (node (ref "ARM_Teensy") (pin "E11") (pinfunction "PTB11_E11") (pintype "passive"))
    )
    (net (code "85") (name "unconnected-(ARM_Teensy-PTB16-PadE10)") (class "Default")
      (node (ref "ARM_Teensy") (pin "E10") (pinfunction "PTB16_E10") (pintype "passive"))
    )
    (net (code "86") (name "unconnected-(ARM_Teensy-PTB17-PadE9)") (class "Default")
      (node (ref "ARM_Teensy") (pin "E9") (pinfunction "PTB17_E9") (pintype "passive"))
    )
    (net (code "87") (name "unconnected-(ARM_Teensy-PTB20-PadD10)") (class "Default")
      (node (ref "ARM_Teensy") (pin "D10") (pinfunction "PTB20_D10") (pintype "passive"))
    )
    (net (code "88") (name "unconnected-(ARM_Teensy-PTB21-PadD9)") (class "Default")
      (node (ref "ARM_Teensy") (pin "D9") (pinfunction "PTB21_D9") (pintype "passive"))
    )
    (net (code "89") (name "unconnected-(ARM_Teensy-PTB22-PadC12)") (class "Default")
      (node (ref "ARM_Teensy") (pin "C12") (pinfunction "PTB22_C12") (pintype "passive"))
    )
    (net (code "90") (name "unconnected-(ARM_Teensy-PTB23-PadC11)") (class "Default")
      (node (ref "ARM_Teensy") (pin "C11") (pinfunction "PTB23_C11") (pintype "passive"))
    )
    (net (code "91") (name "unconnected-(ARM_Teensy-PTC0-PadB12)") (class "Default")
      (node (ref "ARM_Teensy") (pin "B12") (pinfunction "PTC0_B12") (pintype "passive"))
    )
    (net (code "92") (name "unconnected-(ARM_Teensy-PTC1{slash}_LLWU_P6-PadB11)") (class "Default")
      (node (ref "ARM_Teensy") (pin "B11") (pinfunction "PTC1/_LLWU_P6_B11") (pintype "passive"))
    )
    (net (code "93") (name "unconnected-(ARM_Teensy-PTC2-PadA12)") (class "Default")
      (node (ref "ARM_Teensy") (pin "A12") (pinfunction "PTC2_A12") (pintype "passive"))
    )
    (net (code "94") (name "unconnected-(ARM_Teensy-PTC6{slash}_LLWU_P10-PadC8)") (class "Default")
      (node (ref "ARM_Teensy") (pin "C8") (pinfunction "PTC6/_LLWU_P10_C8") (pintype "passive"))
    )
    (net (code "95") (name "unconnected-(ARM_Teensy-PTC7-PadB8)") (class "Default")
      (node (ref "ARM_Teensy") (pin "B8") (pinfunction "PTC7_B8") (pintype "passive"))
    )
    (net (code "96") (name "unconnected-(ARM_Teensy-PTC9-PadD7)") (class "Default")
      (node (ref "ARM_Teensy") (pin "D7") (pinfunction "PTC9_D7") (pintype "passive"))
    )
    (net (code "97") (name "unconnected-(ARM_Teensy-PTC10-PadC7)") (class "Default")
      (node (ref "ARM_Teensy") (pin "C7") (pinfunction "PTC10_C7") (pintype "passive"))
    )
    (net (code "98") (name "unconnected-(ARM_Teensy-PTC11{slash}_LLWU_P11-PadB7)") (class "Default")
      (node (ref "ARM_Teensy") (pin "B7") (pinfunction "PTC11/_LLWU_P11_B7") (pintype "passive"))
    )
    (net (code "99") (name "unconnected-(ARM_Teensy-PTC12-PadA7)") (class "Default")
      (node (ref "ARM_Teensy") (pin "A7") (pinfunction "PTC12_A7") (pintype "passive"))
    )
    (net (code "100") (name "unconnected-(ARM_Teensy-PTC13-PadD6)") (class "Default")
      (node (ref "ARM_Teensy") (pin "D6") (pinfunction "PTC13_D6") (pintype "passive"))
    )
    (net (code "101") (name "unconnected-(ARM_Teensy-PTC14-PadC6)") (class "Default")
      (node (ref "ARM_Teensy") (pin "C6") (pinfunction "PTC14_C6") (pintype "passive"))
    )
    (net (code "102") (name "unconnected-(ARM_Teensy-PTC15-PadB6)") (class "Default")
      (node (ref "ARM_Teensy") (pin "B6") (pinfunction "PTC15_B6") (pintype "passive"))
    )
    (net (code "103") (name "unconnected-(ARM_Teensy-PTC16-PadA6)") (class "Default")
      (node (ref "ARM_Teensy") (pin "A6") (pinfunction "PTC16_A6") (pintype "passive"))
    )
    (net (code "104") (name "unconnected-(ARM_Teensy-PTC17-PadD5)") (class "Default")
      (node (ref "ARM_Teensy") (pin "D5") (pinfunction "PTC17_D5") (pintype "passive"))
    )
    (net (code "105") (name "unconnected-(ARM_Teensy-PTC18-PadC5)") (class "Default")
      (node (ref "ARM_Teensy") (pin "C5") (pinfunction "PTC18_C5") (pintype "passive"))
    )
    (net (code "106") (name "unconnected-(ARM_Teensy-PTC19-PadB5)") (class "Default")
      (node (ref "ARM_Teensy") (pin "B5") (pinfunction "PTC19_B5") (pintype "passive"))
    )
    (net (code "107") (name "unconnected-(ARM_Teensy-PTD1-PadD4)") (class "Default")
      (node (ref "ARM_Teensy") (pin "D4") (pinfunction "PTD1_D4") (pintype "passive"))
    )
    (net (code "108") (name "unconnected-(ARM_Teensy-PTD2{slash}_LLWU_P13-PadC4)") (class "Default")
      (node (ref "ARM_Teensy") (pin "C4") (pinfunction "PTD2/_LLWU_P13_C4") (pintype "passive"))
    )
    (net (code "109") (name "unconnected-(ARM_Teensy-PTD3-PadB4)") (class "Default")
      (node (ref "ARM_Teensy") (pin "B4") (pinfunction "PTD3_B4") (pintype "passive"))
    )
    (net (code "110") (name "unconnected-(ARM_Teensy-PTD4{slash}_LLWU_P14-PadA4)") (class "Default")
      (node (ref "ARM_Teensy") (pin "A4") (pinfunction "PTD4/_LLWU_P14_A4") (pintype "passive"))
    )
    (net (code "111") (name "unconnected-(ARM_Teensy-PTD5-PadA3)") (class "Default")
      (node (ref "ARM_Teensy") (pin "A3") (pinfunction "PTD5_A3") (pintype "passive"))
    )
    (net (code "112") (name "unconnected-(ARM_Teensy-PTD6{slash}_LLWU_P15-PadA2)") (class "Default")
      (node (ref "ARM_Teensy") (pin "A2") (pinfunction "PTD6/_LLWU_P15_A2") (pintype "passive"))
    )
    (net (code "113") (name "unconnected-(ARM_Teensy-PTD7-PadA1)") (class "Default")
      (node (ref "ARM_Teensy") (pin "A1") (pinfunction "PTD7_A1") (pintype "passive"))
    )
    (net (code "114") (name "unconnected-(ARM_Teensy-PTD8{slash}LLWU_P24-PadC9)") (class "Default")
      (node (ref "ARM_Teensy") (pin "C9") (pinfunction "PTD8/LLWU_P24_C9") (pintype "passive"))
    )
    (net (code "115") (name "unconnected-(ARM_Teensy-PTD9-PadB9)") (class "Default")
      (node (ref "ARM_Teensy") (pin "B9") (pinfunction "PTD9_B9") (pintype "passive"))
    )
    (net (code "116") (name "unconnected-(ARM_Teensy-PTD10-PadB3)") (class "Default")
      (node (ref "ARM_Teensy") (pin "B3") (pinfunction "PTD10_B3") (pintype "passive"))
    )
    (net (code "117") (name "unconnected-(ARM_Teensy-PTD11{slash}LLWU_P25-PadB2)") (class "Default")
      (node (ref "ARM_Teensy") (pin "B2") (pinfunction "PTD11/LLWU_P25_B2") (pintype "passive"))
    )
    (net (code "118") (name "unconnected-(ARM_Teensy-PTD12-PadB1)") (class "Default")
      (node (ref "ARM_Teensy") (pin "B1") (pinfunction "PTD12_B1") (pintype "passive"))
    )
    (net (code "119") (name "unconnected-(ARM_Teensy-PTD13-PadC3)") (class "Default")
      (node (ref "ARM_Teensy") (pin "C3") (pinfunction "PTD13_C3") (pintype "passive"))
    )
    (net (code "120") (name "unconnected-(ARM_Teensy-PTD14-PadC2)") (class "Default")
      (node (ref "ARM_Teensy") (pin "C2") (pinfunction "PTD14_C2") (pintype "passive"))
    )
    (net (code "121") (name "unconnected-(ARM_Teensy-PTD15-PadC1)") (class "Default")
      (node (ref "ARM_Teensy") (pin "C1") (pinfunction "PTD15_C1") (pintype "passive"))
    )
    (net (code "122") (name "unconnected-(ARM_Teensy-PTE0-PadD3)") (class "Default")
      (node (ref "ARM_Teensy") (pin "D3") (pinfunction "PTE0_D3") (pintype "passive"))
    )
    (net (code "123") (name "unconnected-(ARM_Teensy-PTE1{slash}LLWU_P0-PadD2)") (class "Default")
      (node (ref "ARM_Teensy") (pin "D2") (pinfunction "PTE1/LLWU_P0_D2") (pintype "passive"))
    )
    (net (code "124") (name "unconnected-(ARM_Teensy-PTE2{slash}LLWU_P1-PadD1)") (class "Default")
      (node (ref "ARM_Teensy") (pin "D1") (pinfunction "PTE2/LLWU_P1_D1") (pintype "passive"))
    )
    (net (code "125") (name "unconnected-(ARM_Teensy-PTE3-PadE4)") (class "Default")
      (node (ref "ARM_Teensy") (pin "E4") (pinfunction "PTE3_E4") (pintype "passive"))
    )
    (net (code "126") (name "unconnected-(ARM_Teensy-PTE4{slash}LLWU_P2-PadE3)") (class "Default")
      (node (ref "ARM_Teensy") (pin "E3") (pinfunction "PTE4/LLWU_P2_E3") (pintype "passive"))
    )
    (net (code "127") (name "unconnected-(ARM_Teensy-PTE5-PadE2)") (class "Default")
      (node (ref "ARM_Teensy") (pin "E2") (pinfunction "PTE5_E2") (pintype "passive"))
    )
    (net (code "128") (name "unconnected-(ARM_Teensy-PTE6{slash}LLWU_P16-PadE1)") (class "Default")
      (node (ref "ARM_Teensy") (pin "E1") (pinfunction "PTE6/LLWU_P16_E1") (pintype "passive"))
    )
    (net (code "129") (name "unconnected-(ARM_Teensy-PTE7-PadF4)") (class "Default")
      (node (ref "ARM_Teensy") (pin "F4") (pinfunction "PTE7_F4") (pintype "passive"))
    )
    (net (code "130") (name "unconnected-(ARM_Teensy-PTE8-PadF3)") (class "Default")
      (node (ref "ARM_Teensy") (pin "F3") (pinfunction "PTE8_F3") (pintype "passive"))
    )
    (net (code "131") (name "unconnected-(ARM_Teensy-PTE9{slash}LLWU_P17-PadF2)") (class "Default")
      (node (ref "ARM_Teensy") (pin "F2") (pinfunction "PTE9/LLWU_P17_F2") (pintype "passive"))
    )
    (net (code "132") (name "unconnected-(ARM_Teensy-PTE10{slash}LLWU_P18-PadF1)") (class "Default")
      (node (ref "ARM_Teensy") (pin "F1") (pinfunction "PTE10/LLWU_P18_F1") (pintype "passive"))
    )
    (net (code "133") (name "unconnected-(ARM_Teensy-PTE11-PadG4)") (class "Default")
      (node (ref "ARM_Teensy") (pin "G4") (pinfunction "PTE11_G4") (pintype "passive"))
    )
    (net (code "134") (name "unconnected-(ARM_Teensy-PTE12-PadG3)") (class "Default")
      (node (ref "ARM_Teensy") (pin "G3") (pinfunction "PTE12_G3") (pintype "passive"))
    )
    (net (code "135") (name "unconnected-(ARM_Teensy-PTE26-PadK4)") (class "Default")
      (node (ref "ARM_Teensy") (pin "K4") (pinfunction "PTE26_K4") (pintype "passive"))
    )
    (net (code "136") (name "unconnected-(ARM_Teensy-PTE27-PadJ4)") (class "Default")
      (node (ref "ARM_Teensy") (pin "J4") (pinfunction "PTE27_J4") (pintype "passive"))
    )
    (net (code "137") (name "unconnected-(ARM_Teensy-PTE28-PadH4)") (class "Default")
      (node (ref "ARM_Teensy") (pin "H4") (pinfunction "PTE28_H4") (pintype "passive"))
    )
    (net (code "138") (name "unconnected-(ARM_Teensy-RTC_WAKEUP_B-PadL5)") (class "Default")
      (node (ref "ARM_Teensy") (pin "L5") (pinfunction "RTC_WAKEUP_B_L5") (pintype "passive"))
    )
    (net (code "139") (name "unconnected-(ARM_Teensy-USB1_DM-PadK1)") (class "Default")
      (node (ref "ARM_Teensy") (pin "K1") (pinfunction "USB1_DM_K1") (pintype "passive"))
    )
    (net (code "140") (name "unconnected-(ARM_Teensy-USB1_DP-PadJ1)") (class "Default")
      (node (ref "ARM_Teensy") (pin "J1") (pinfunction "USB1_DP_J1") (pintype "passive"))
    )
    (net (code "141") (name "unconnected-(ARM_Teensy-USB1_VBUS-PadL1)") (class "Default")
      (node (ref "ARM_Teensy") (pin "L1") (pinfunction "USB1_VBUS_L1") (pintype "passive"))
    )
    (net (code "142") (name "unconnected-(ARM_Teensy-VREG_IN1-PadJ2)") (class "Default")
      (node (ref "ARM_Teensy") (pin "J2") (pinfunction "VREG_IN1_J2") (pintype "passive"))
    )
    (net (code "143") (name "unconnected-(Boot_Teensy-PTA0{slash}IRQ_0-Pad14)") (class "Default")
      (node (ref "Boot_Teensy") (pin "14") (pinfunction "PTA0/IRQ_0_14") (pintype "passive"))
    )
    (net (code "144") (name "unconnected-(Boot_Teensy-PTA1{slash}IRQ_1{slash}LPTMR0_ALT1-Pad15)") (class "Default")
      (node (ref "Boot_Teensy") (pin "15") (pinfunction "PTA1/IRQ_1/LPTMR0_ALT1_15") (pintype "passive"))
    )
    (net (code "145") (name "unconnected-(Boot_Teensy-PTA2-Pad16)") (class "Default")
      (node (ref "Boot_Teensy") (pin "16") (pinfunction "PTA2_16") (pintype "passive"))
    )
    (net (code "146") (name "unconnected-(Boot_Teensy-PTA3-Pad3)") (class "Default")
      (node (ref "Boot_Teensy") (pin "3") (pinfunction "PTA3_3") (pintype "passive"))
    )
    (net (code "147") (name "unconnected-(Boot_Teensy-PTA5-Pad5)") (class "Default")
      (node (ref "Boot_Teensy") (pin "5") (pinfunction "PTA5_5") (pintype "passive"))
    )
    (net (code "148") (name "unconnected-(Boot_Teensy-PTB3{slash}IRQ_10-Pad11)") (class "Default")
      (node (ref "Boot_Teensy") (pin "11") (pinfunction "PTB3/IRQ_10_11") (pintype "passive"))
    )
    (net (code "149") (name "unconnected-(Boot_Teensy-PTB4{slash}IRQ_11-Pad12)") (class "Default")
      (node (ref "Boot_Teensy") (pin "12") (pinfunction "PTB4/IRQ_11_12") (pintype "passive"))
    )
    (net (code "150") (name "unconnected-(SW1-Pad1)") (class "Default")
      (node (ref "SW1") (pin "1") (pinfunction "1_1") (pintype "passive"))
    )
    (net (code "151") (name "unconnected-(SW1-Pad3)") (class "Default")
      (node (ref "SW1") (pin "3") (pinfunction "3_3") (pintype "passive"))
    )
    (net (code "152") (name "unconnected-(USB_Teensy-Pad4)") (class "Default")
      (node (ref "USB_Teensy") (pin "4") (pinfunction "4_4") (pintype "passive"))
    )
    (net (code "153") (name "unconnected-(USB_Teensy-Pad6)") (class "Default")
      (node (ref "USB_Teensy") (pin "6") (pinfunction "6_6") (pintype "passive"))
    )
    (net (code "154") (name "unconnected-(USB_Teensy-Pad7)") (class "Default")
      (node (ref "USB_Teensy") (pin "7") (pinfunction "7_7") (pintype "passive"))
    )
    (net (code "155") (name "unconnected-(USB_Teensy-Pad8)") (class "Default")
      (node (ref "USB_Teensy") (pin "8") (pinfunction "8_8") (pintype "passive"))
    )
    (net (code "156") (name "unconnected-(USB_Teensy-Pad9)") (class "Default")
      (node (ref "USB_Teensy") (pin "9") (pinfunction "9_9") (pintype "passive"))
    )
    (net (code "157") (name "unconnected-(USB_Teensy-Pad10)") (class "Default")
      (node (ref "USB_Teensy") (pin "10") (pinfunction "10_10") (pintype "passive"))
    )
    (net (code "158") (name "unconnected-(USB_Teensy-Pad11)") (class "Default")
      (node (ref "USB_Teensy") (pin "11") (pinfunction "11_11") (pintype "passive"))
    )
    (net (code "159") (name "unconnected-(VREG_Teensy-N{slash}C-Pad3)") (class "Default")
      (node (ref "VREG_Teensy") (pin "3") (pinfunction "N/C_3") (pintype "passive"))
    )
  )
)
